# St3025_Servo_Schematic.net
KiCad netlist of a schematic drawn in Altium Designer
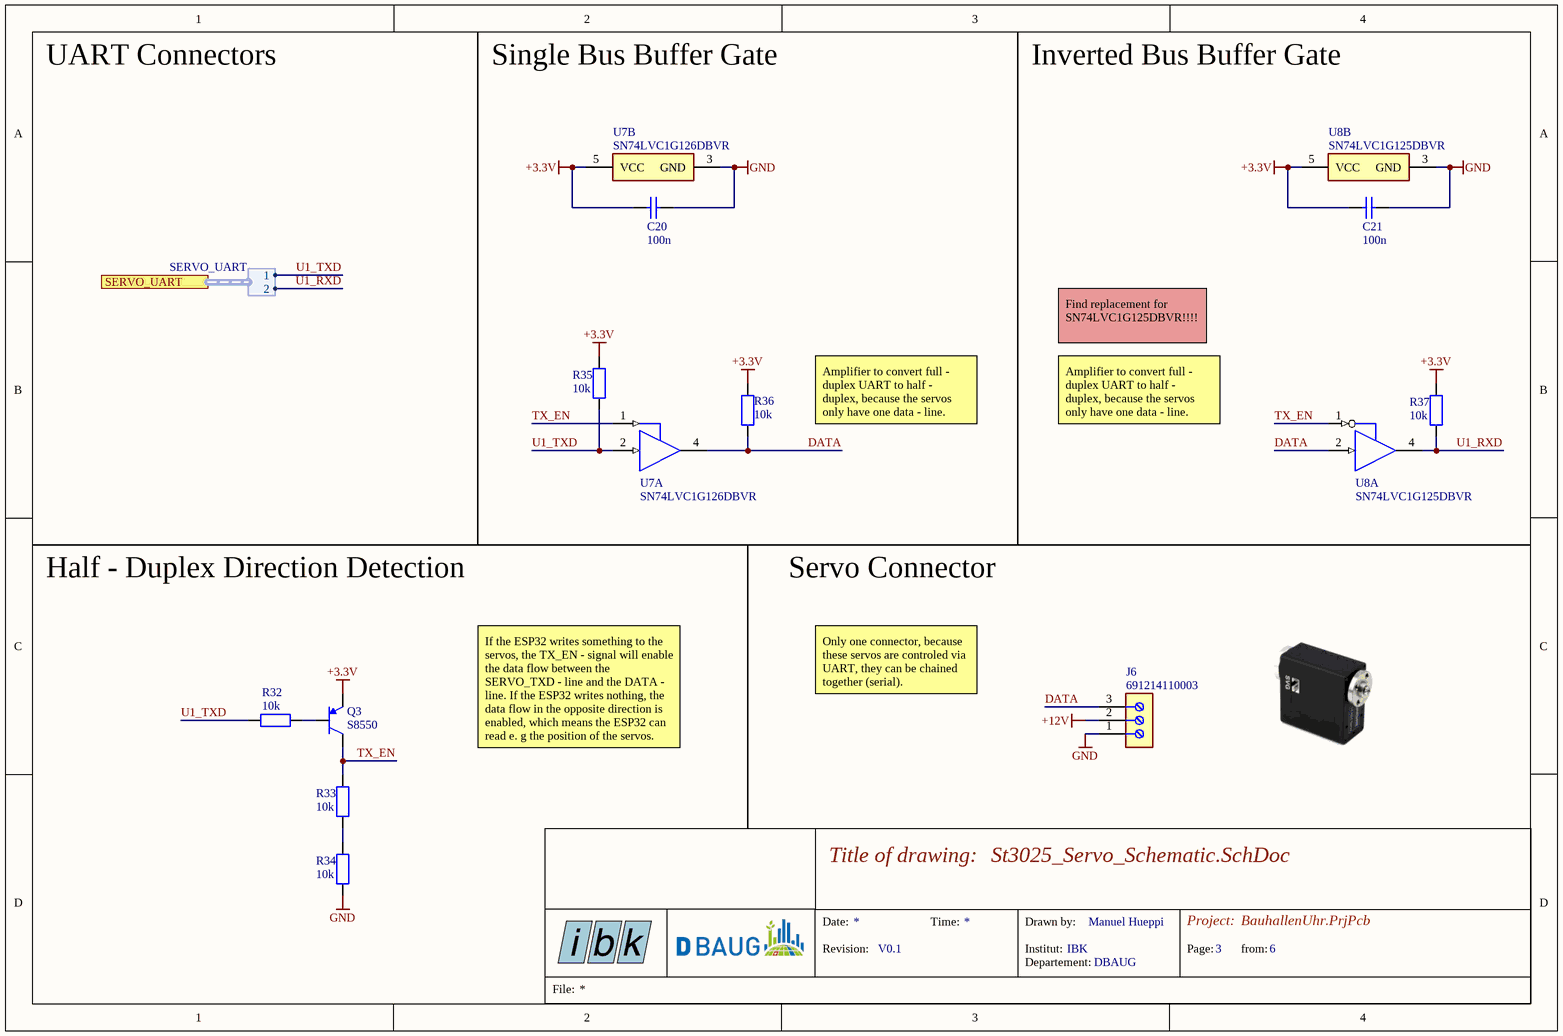
[diagram p0: St3025_Servo_Schematic.SchDoc]

(export (version "E")
  (design (tool "Eeschema 10.0.6"))
  (components
    (comp (ref "C20")
      (value "100n")
      (footprint "PCB_Altium_Library_Manuel:0603_CAPACITOR")
      (description "0603")
      (libsource (lib "Schematic_Altium_Library_Manuel") (part "Capacitor"))
    )
    (comp (ref "C21")
      (value "100n")
      (footprint "PCB_Altium_Library_Manuel:0603_CAPACITOR")
      (description "0603")
      (libsource (lib "Schematic_Altium_Library_Manuel") (part "Capacitor"))
    )
    (comp (ref "J6")
      (value "691214110003")
      (footprint "PCB_Altium_Library_Manuel:Screw_Connector")
      (description "691214110003 Wurth Elektronik")
      (libsource (lib "Schematic_Altium_Library_Manuel") (part "Screw_Connector"))
    )
    (comp (ref "Q3")
      (value "S8550")
      (footprint "PCB_Altium_Library_Manuel:PNP_Bipolar_Transistor")
      (description "Bipolar (BJT) Transistor PNP 25 V 500 mA 150MHz 300 mW Surface Mount SOT-23.")
      (libsource (lib "Schematic_Altium_Library_Manuel") (part "PNP_Bipolar_Transistor"))
    )
    (comp (ref "R32")
      (value "10k")
      (footprint "PCB_Altium_Library_Manuel:0603_Resistor")
      (description "0603")
      (libsource (lib "") (part "Resistor_1"))
    )
    (comp (ref "R33")
      (value "10k")
      (footprint "PCB_Altium_Library_Manuel:0603_Resistor")
      (description "0603")
      (libsource (lib "Schematic_Altium_Library_Manuel") (part "Resistor"))
    )
    (comp (ref "R34")
      (value "10k")
      (footprint "PCB_Altium_Library_Manuel:0603_Resistor")
      (description "0603")
      (libsource (lib "Schematic_Altium_Library_Manuel") (part "Resistor"))
    )
    (comp (ref "R35")
      (value "10k")
      (footprint "PCB_Altium_Library_Manuel:0603_Resistor")
      (description "0603")
      (libsource (lib "Schematic_Altium_Library_Manuel") (part "Resistor"))
    )
    (comp (ref "R36")
      (value "10k")
      (footprint "PCB_Altium_Library_Manuel:0603_Resistor")
      (description "0603")
      (libsource (lib "Schematic_Altium_Library_Manuel") (part "Resistor"))
    )
    (comp (ref "R37")
      (value "10k")
      (footprint "PCB_Altium_Library_Manuel:0603_Resistor")
      (description "0603")
      (libsource (lib "Schematic_Altium_Library_Manuel") (part "Resistor"))
    )
    (comp (ref "U7")
      (value "SN74LVC1G126DBVR")
      (footprint "PCB_Altium_Library_Manuel:DBV0005A_L_Single_Bus_Buffer_Gate")
      (description "Single Bus Buffer Gate With 3-State Outputs, DBV0005A, LARGE T&R.")
      (libsource (lib "Schematic_Altium_Library_Manuel") (part "Single_Bus_Buffer_Gate"))
    )
    (comp (ref "U8")
      (value "SN74LVC1G125DBVR")
      (footprint "PCB_Altium_Library_Manuel:DBV0005A_L_Single_Bus_Buffer_Gate")
      (description "Single Bus Buffer Gate With 3-State Outputs, DBV0005A, LARGE T&R.")
      (libsource (lib "Schematic_Altium_Library_Manuel") (part "Single_Bus_Buffer_Gate_Inverted"))
    )
  )
  (nets
    (net (code "2") (name "+3.3V") (class "Default")
      (node (ref "C20") (pin "2") (pinfunction "2_2") (pintype "passive"))
      (node (ref "C21") (pin "2") (pinfunction "2_2") (pintype "passive"))
      (node (ref "Q3") (pin "2") (pinfunction "E_2") (pintype "passive"))
      (node (ref "R35") (pin "2") (pinfunction "2_2") (pintype "passive"))
      (node (ref "R36") (pin "2") (pinfunction "2_2") (pintype "passive"))
      (node (ref "R37") (pin "2") (pinfunction "2_2") (pintype "passive"))
      (node (ref "U7") (pin "5") (pinfunction "VCC_5") (pintype "power_in"))
      (node (ref "U8") (pin "5") (pinfunction "VCC_5") (pintype "power_in"))
    )
    (net (code "3") (name "+12V") (class "Default")
      (node (ref "J6") (pin "2") (pinfunction "2_2") (pintype "passive"))
    )
    (net (code "4") (name "/DATA") (class "Default")
      (node (ref "J6") (pin "3") (pinfunction "3_3") (pintype "passive"))
      (node (ref "R36") (pin "1") (pinfunction "1_1") (pintype "passive"))
      (node (ref "U7") (pin "4") (pinfunction "Y_4") (pintype "tri_state"))
      (node (ref "U8") (pin "2") (pinfunction "A_2") (pintype "input"))
    )
    (net (code "5") (name "/TX_EN") (class "Default")
      (node (ref "Q3") (pin "3") (pinfunction "C_3") (pintype "passive"))
      (node (ref "R33") (pin "2") (pinfunction "2_2") (pintype "passive"))
      (node (ref "U7") (pin "1") (pinfunction "OE_1") (pintype "input"))
      (node (ref "U8") (pin "1") (pinfunction "OE_1") (pintype "input"))
    )
    (net (code "6") (name "/U1_RXD") (class "Default")
      (node (ref "R37") (pin "1") (pinfunction "1_1") (pintype "passive"))
      (node (ref "U8") (pin "4") (pinfunction "Y_4") (pintype "tri_state"))
    )
    (net (code "7") (name "/U1_TXD") (class "Default")
      (node (ref "R32") (pin "2") (pinfunction "2_2") (pintype "passive"))
      (node (ref "R35") (pin "1") (pinfunction "1_1") (pintype "passive"))
      (node (ref "U7") (pin "2") (pinfunction "A_2") (pintype "input"))
    )
    (net (code "9") (name "GND") (class "Default")
      (node (ref "C20") (pin "1") (pinfunction "1_1") (pintype "passive"))
      (node (ref "C21") (pin "1") (pinfunction "1_1") (pintype "passive"))
      (node (ref "J6") (pin "1") (pinfunction "1_1") (pintype "passive"))
      (node (ref "R34") (pin "1") (pinfunction "1_1") (pintype "passive"))
      (node (ref "U7") (pin "3") (pinfunction "GND_3") (pintype "power_in"))
      (node (ref "U8") (pin "3") (pinfunction "GND_3") (pintype "power_in"))
    )
    (net (code "10") (name "Net-(Q3-B)") (class "Default")
      (node (ref "Q3") (pin "1") (pinfunction "B_1") (pintype "passive"))
      (node (ref "R32") (pin "1") (pinfunction "1_1") (pintype "passive"))
    )
    (net (code "11") (name "Net-(R33-Pad1)") (class "Default")
      (node (ref "R33") (pin "1") (pinfunction "1_1") (pintype "passive"))
      (node (ref "R34") (pin "2") (pinfunction "2_2") (pintype "passive"))
    )
  )
)
